# SCH_rhythm-pad_2026-10-07.net
KiCad netlist of a schematic drawn in EasyEDA
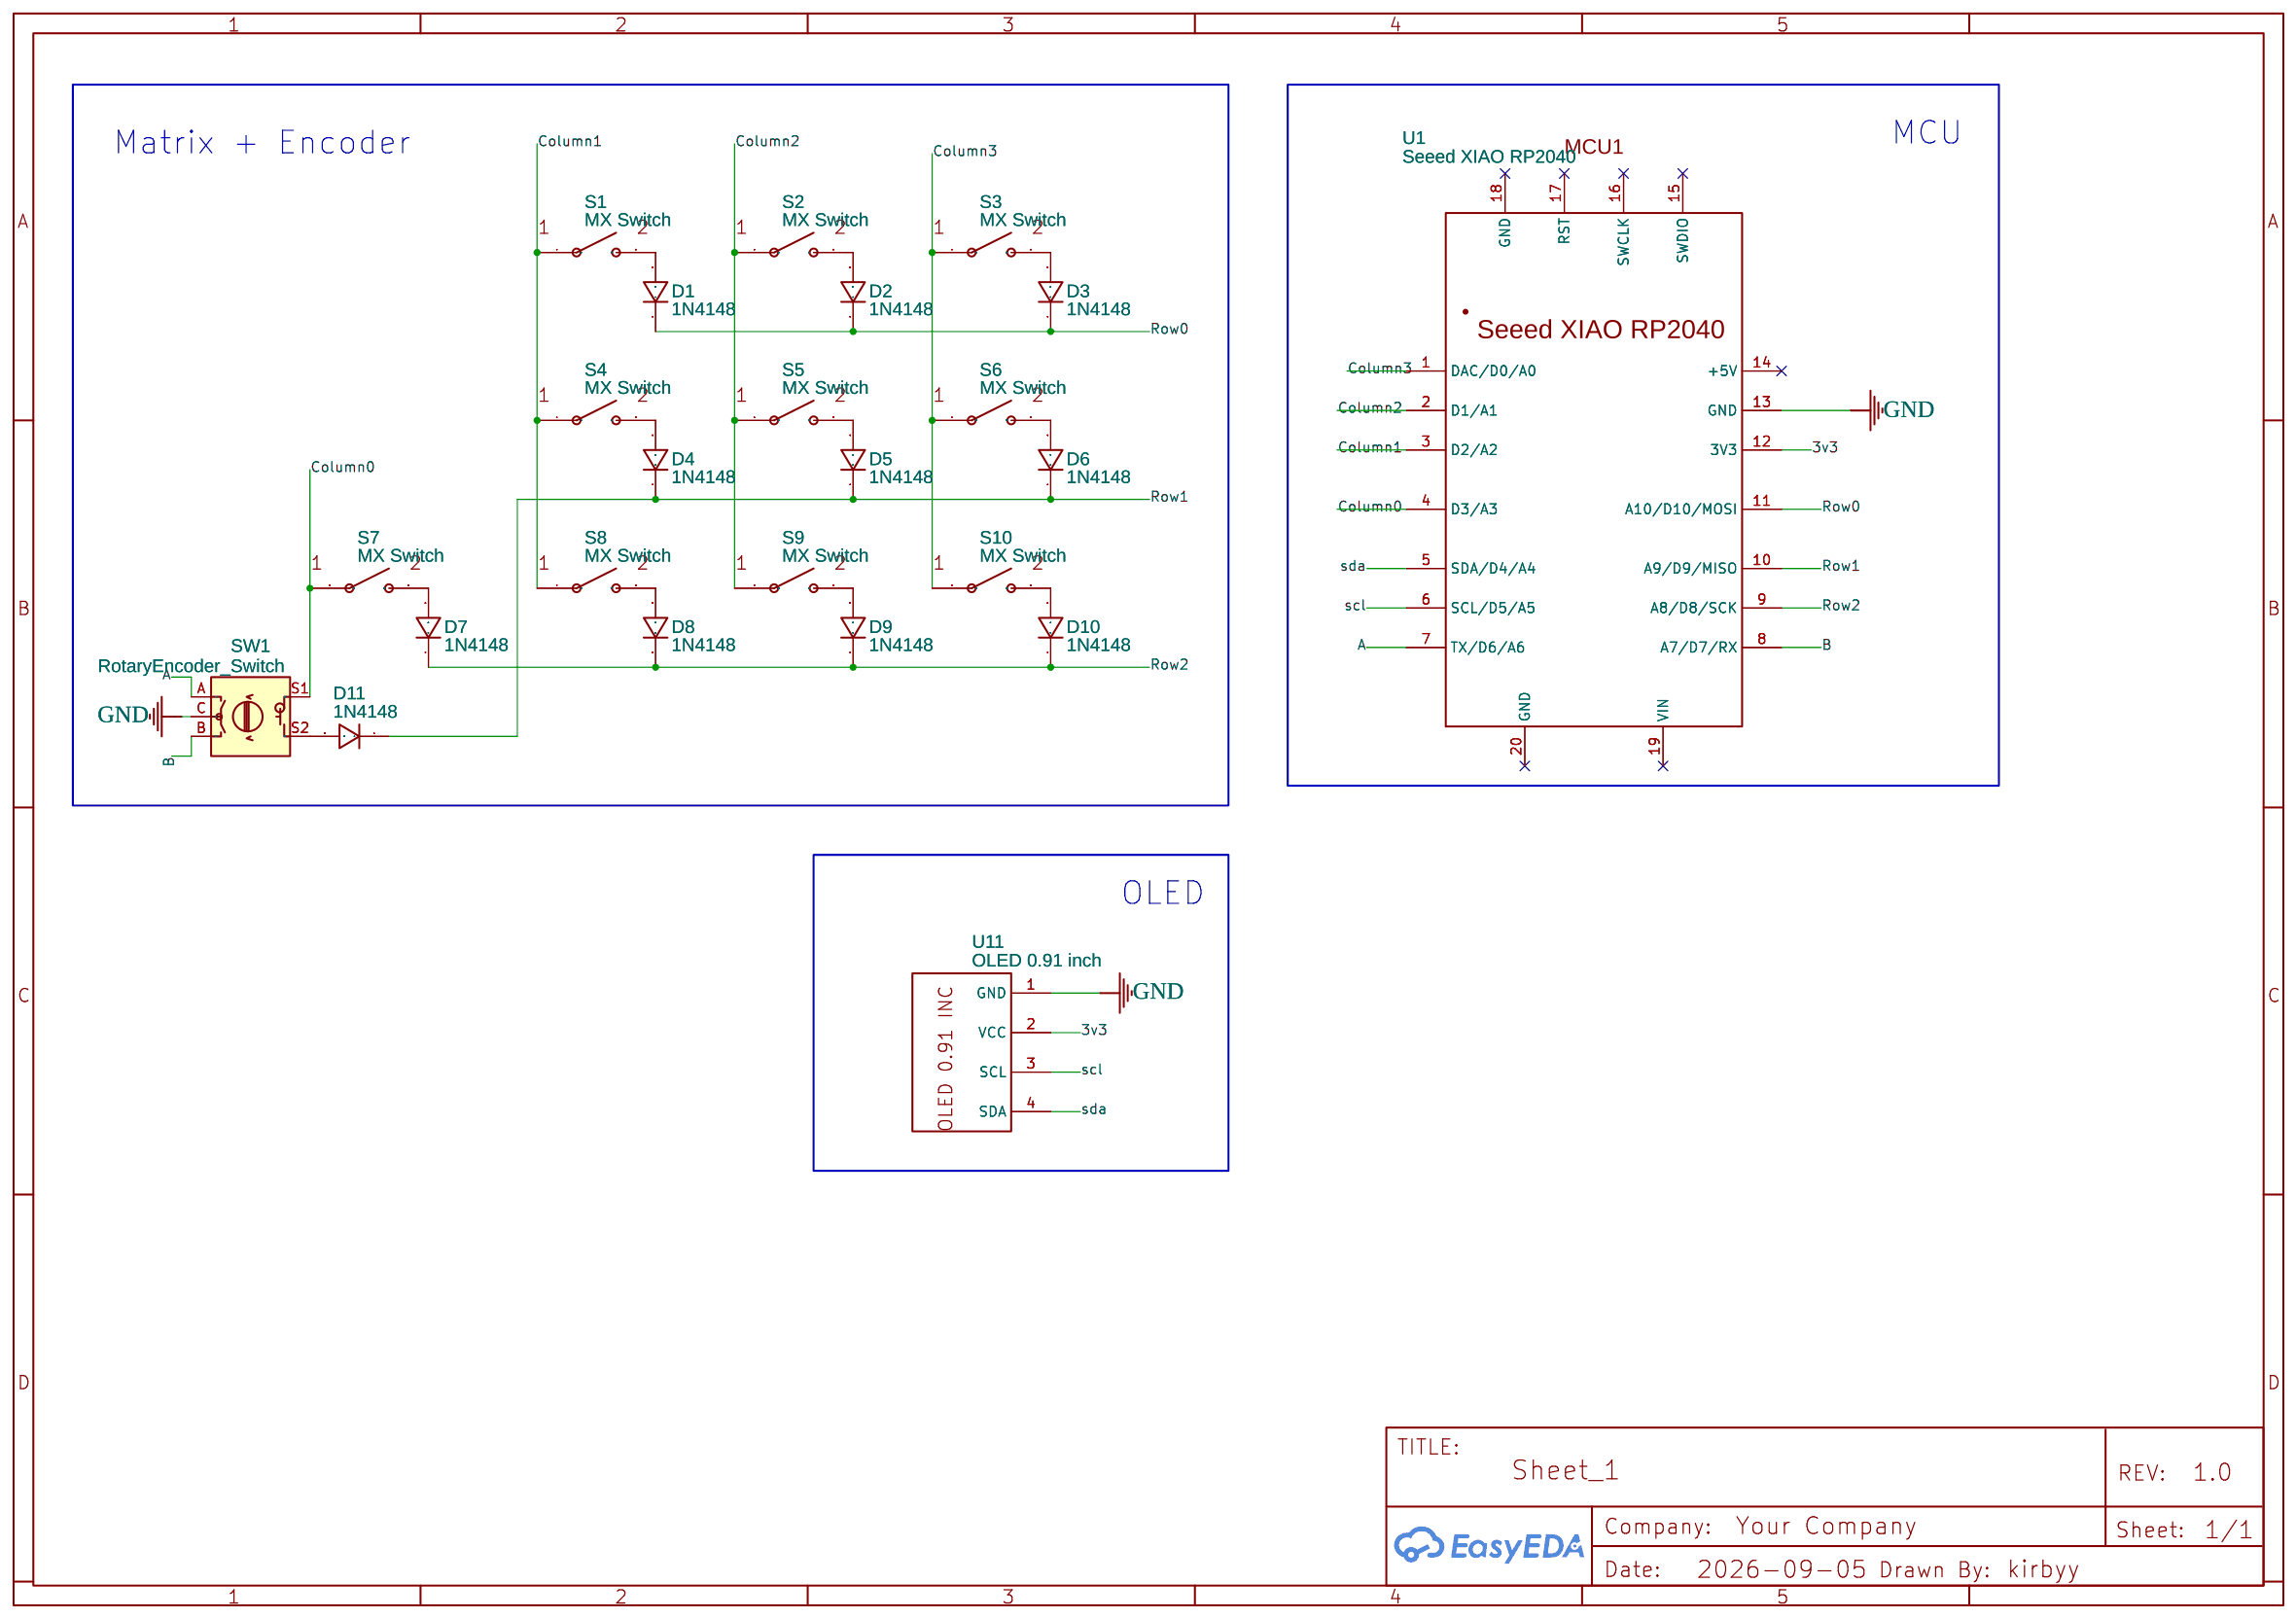
[diagram p0: schematic sheet]

(export (version "E")
  (design (tool "Eeschema 10.0.6"))
  (components
    (comp (ref "D1")
      (value "1N4148")
      (fields (field (name "Manufacturer") "STMicroelectronics"))
      (libsource (lib "") (part "1N4148"))
    )
    (comp (ref "D2")
      (value "1N4148")
      (fields (field (name "Manufacturer") "STMicroelectronics"))
      (libsource (lib "") (part "1N4148"))
    )
    (comp (ref "D3")
      (value "1N4148")
      (fields (field (name "Manufacturer") "STMicroelectronics"))
      (libsource (lib "") (part "1N4148"))
    )
    (comp (ref "D4")
      (value "1N4148")
      (fields (field (name "Manufacturer") "STMicroelectronics"))
      (libsource (lib "") (part "1N4148"))
    )
    (comp (ref "D5")
      (value "1N4148")
      (fields (field (name "Manufacturer") "STMicroelectronics"))
      (libsource (lib "") (part "1N4148"))
    )
    (comp (ref "D6")
      (value "1N4148")
      (fields (field (name "Manufacturer") "STMicroelectronics"))
      (libsource (lib "") (part "1N4148"))
    )
    (comp (ref "D7")
      (value "1N4148")
      (fields (field (name "Manufacturer") "STMicroelectronics"))
      (libsource (lib "") (part "1N4148"))
    )
    (comp (ref "D8")
      (value "1N4148")
      (fields (field (name "Manufacturer") "STMicroelectronics"))
      (libsource (lib "") (part "1N4148"))
    )
    (comp (ref "D9")
      (value "1N4148")
      (fields (field (name "Manufacturer") "STMicroelectronics"))
      (libsource (lib "") (part "1N4148"))
    )
    (comp (ref "D10")
      (value "1N4148")
      (fields (field (name "Manufacturer") "STMicroelectronics"))
      (libsource (lib "") (part "1N4148"))
    )
    (comp (ref "D11")
      (value "1N4148")
      (fields (field (name "Manufacturer") "STMicroelectronics"))
      (libsource (lib "") (part "1N4148_1"))
    )
    (comp (ref "S1") (value "MX Switch") (libsource (lib "") (part "Cherry MX Mechanical Keyboard Switch")))
    (comp (ref "S2") (value "MX Switch") (libsource (lib "") (part "Cherry MX Mechanical Keyboard Switch")))
    (comp (ref "S3") (value "MX Switch") (libsource (lib "") (part "Cherry MX Mechanical Keyboard Switch")))
    (comp (ref "S4") (value "MX Switch") (libsource (lib "") (part "Cherry MX Mechanical Keyboard Switch")))
    (comp (ref "S5") (value "MX Switch") (libsource (lib "") (part "Cherry MX Mechanical Keyboard Switch")))
    (comp (ref "S6") (value "MX Switch") (libsource (lib "") (part "Cherry MX Mechanical Keyboard Switch")))
    (comp (ref "S7") (value "MX Switch") (libsource (lib "") (part "Cherry MX Mechanical Keyboard Switch")))
    (comp (ref "S8") (value "MX Switch") (libsource (lib "") (part "Cherry MX Mechanical Keyboard Switch")))
    (comp (ref "S9") (value "MX Switch") (libsource (lib "") (part "Cherry MX Mechanical Keyboard Switch")))
    (comp (ref "S10") (value "MX Switch") (libsource (lib "") (part "Cherry MX Mechanical Keyboard Switch")))
    (comp (ref "SW1") (value "RotaryEncoder_Switch") (libsource (lib "") (part "RotaryEncoder_Switch")))
    (comp (ref "U1")
      (value "Seeed XIAO RP2040")
      (fields (field (name "Manufacturer Part") "Seeed XIAO RP2040("))
      (libsource (lib "") (part "Seeed XIAO RP2040"))
    )
    (comp (ref "U11") (value "OLED 0.91 inch") (libsource (lib "") (part "OLED 0.91 inch")))
  )
  (nets
    (net (code "1") (name "/3v3") (class "Default")
      (node (ref "U1") (pin "12") (pinfunction "3V3_12") (pintype "unspecified"))
      (node (ref "U11") (pin "2") (pinfunction "VCC_2") (pintype "unspecified"))
    )
    (net (code "2") (name "/A") (class "Default")
      (node (ref "SW1") (pin "A") (pinfunction "A_A") (pintype "unspecified"))
      (node (ref "U1") (pin "7") (pinfunction "TX/D6/A6_7") (pintype "unspecified"))
    )
    (net (code "3") (name "/B") (class "Default")
      (node (ref "SW1") (pin "B") (pinfunction "B_B") (pintype "unspecified"))
      (node (ref "U1") (pin "8") (pinfunction "A7/D7/RX_8") (pintype "unspecified"))
    )
    (net (code "4") (name "/Column0") (class "Default")
      (node (ref "S7") (pin "1") (pinfunction "1_1") (pintype "unspecified"))
      (node (ref "SW1") (pin "S1") (pinfunction "S1_S1") (pintype "unspecified"))
      (node (ref "U1") (pin "4") (pinfunction "D3/A3_4") (pintype "unspecified"))
    )
    (net (code "5") (name "/Column1") (class "Default")
      (node (ref "S1") (pin "1") (pinfunction "1_1") (pintype "unspecified"))
      (node (ref "S4") (pin "1") (pinfunction "1_1") (pintype "unspecified"))
      (node (ref "S8") (pin "1") (pinfunction "1_1") (pintype "unspecified"))
      (node (ref "U1") (pin "3") (pinfunction "D2/A2_3") (pintype "unspecified"))
    )
    (net (code "6") (name "/Column2") (class "Default")
      (node (ref "S2") (pin "1") (pinfunction "1_1") (pintype "unspecified"))
      (node (ref "S5") (pin "1") (pinfunction "1_1") (pintype "unspecified"))
      (node (ref "S9") (pin "1") (pinfunction "1_1") (pintype "unspecified"))
      (node (ref "U1") (pin "2") (pinfunction "D1/A1_2") (pintype "unspecified"))
    )
    (net (code "7") (name "/Column3") (class "Default")
      (node (ref "S10") (pin "1") (pinfunction "1_1") (pintype "unspecified"))
      (node (ref "S3") (pin "1") (pinfunction "1_1") (pintype "unspecified"))
      (node (ref "S6") (pin "1") (pinfunction "1_1") (pintype "unspecified"))
      (node (ref "U1") (pin "1") (pinfunction "DAC/D0/A0_1") (pintype "unspecified"))
    )
    (net (code "8") (name "/Row0") (class "Default")
      (node (ref "D1") (pin "1") (pinfunction "1_1") (pintype "unspecified"))
      (node (ref "D2") (pin "1") (pinfunction "1_1") (pintype "unspecified"))
      (node (ref "D3") (pin "1") (pinfunction "1_1") (pintype "unspecified"))
      (node (ref "U1") (pin "11") (pinfunction "A10/D10/MOSI_11") (pintype "unspecified"))
    )
    (net (code "9") (name "/Row1") (class "Default")
      (node (ref "D11") (pin "1") (pinfunction "1_1") (pintype "unspecified"))
      (node (ref "D4") (pin "1") (pinfunction "1_1") (pintype "unspecified"))
      (node (ref "D5") (pin "1") (pinfunction "1_1") (pintype "unspecified"))
      (node (ref "D6") (pin "1") (pinfunction "1_1") (pintype "unspecified"))
      (node (ref "U1") (pin "10") (pinfunction "A9/D9/MISO_10") (pintype "unspecified"))
    )
    (net (code "10") (name "/Row2") (class "Default")
      (node (ref "D10") (pin "1") (pinfunction "1_1") (pintype "unspecified"))
      (node (ref "D7") (pin "1") (pinfunction "1_1") (pintype "unspecified"))
      (node (ref "D8") (pin "1") (pinfunction "1_1") (pintype "unspecified"))
      (node (ref "D9") (pin "1") (pinfunction "1_1") (pintype "unspecified"))
      (node (ref "U1") (pin "9") (pinfunction "A8/D8/SCK_9") (pintype "unspecified"))
    )
    (net (code "11") (name "/scl") (class "Default")
      (node (ref "U1") (pin "6") (pinfunction "SCL/D5/A5_6") (pintype "unspecified"))
      (node (ref "U11") (pin "3") (pinfunction "SCL_3") (pintype "unspecified"))
    )
    (net (code "12") (name "/sda") (class "Default")
      (node (ref "U1") (pin "5") (pinfunction "SDA/D4/A4_5") (pintype "unspecified"))
      (node (ref "U11") (pin "4") (pinfunction "SDA_4") (pintype "unspecified"))
    )
    (net (code "13") (name "GND") (class "Default")
      (node (ref "SW1") (pin "C") (pinfunction "C_C") (pintype "unspecified"))
      (node (ref "U1") (pin "13") (pinfunction "GND_13") (pintype "unspecified"))
      (node (ref "U11") (pin "1") (pinfunction "GND_1") (pintype "unspecified"))
    )
    (net (code "14") (name "Net-(D1-Pad2)") (class "Default")
      (node (ref "D1") (pin "2") (pinfunction "2_2") (pintype "unspecified"))
      (node (ref "S1") (pin "2") (pinfunction "2_2") (pintype "unspecified"))
    )
    (net (code "15") (name "Net-(D2-Pad2)") (class "Default")
      (node (ref "D2") (pin "2") (pinfunction "2_2") (pintype "unspecified"))
      (node (ref "S2") (pin "2") (pinfunction "2_2") (pintype "unspecified"))
    )
    (net (code "16") (name "Net-(D3-Pad2)") (class "Default")
      (node (ref "D3") (pin "2") (pinfunction "2_2") (pintype "unspecified"))
      (node (ref "S3") (pin "2") (pinfunction "2_2") (pintype "unspecified"))
    )
    (net (code "17") (name "Net-(D4-Pad2)") (class "Default")
      (node (ref "D4") (pin "2") (pinfunction "2_2") (pintype "unspecified"))
      (node (ref "S4") (pin "2") (pinfunction "2_2") (pintype "unspecified"))
    )
    (net (code "18") (name "Net-(D5-Pad2)") (class "Default")
      (node (ref "D5") (pin "2") (pinfunction "2_2") (pintype "unspecified"))
      (node (ref "S5") (pin "2") (pinfunction "2_2") (pintype "unspecified"))
    )
    (net (code "19") (name "Net-(D6-Pad2)") (class "Default")
      (node (ref "D6") (pin "2") (pinfunction "2_2") (pintype "unspecified"))
      (node (ref "S6") (pin "2") (pinfunction "2_2") (pintype "unspecified"))
    )
    (net (code "20") (name "Net-(D7-Pad2)") (class "Default")
      (node (ref "D7") (pin "2") (pinfunction "2_2") (pintype "unspecified"))
      (node (ref "S7") (pin "2") (pinfunction "2_2") (pintype "unspecified"))
    )
    (net (code "21") (name "Net-(D8-Pad2)") (class "Default")
      (node (ref "D8") (pin "2") (pinfunction "2_2") (pintype "unspecified"))
      (node (ref "S8") (pin "2") (pinfunction "2_2") (pintype "unspecified"))
    )
    (net (code "22") (name "Net-(D9-Pad2)") (class "Default")
      (node (ref "D9") (pin "2") (pinfunction "2_2") (pintype "unspecified"))
      (node (ref "S9") (pin "2") (pinfunction "2_2") (pintype "unspecified"))
    )
    (net (code "23") (name "Net-(D10-Pad2)") (class "Default")
      (node (ref "D10") (pin "2") (pinfunction "2_2") (pintype "unspecified"))
      (node (ref "S10") (pin "2") (pinfunction "2_2") (pintype "unspecified"))
    )
    (net (code "24") (name "Net-(D11-Pad2)") (class "Default")
      (node (ref "D11") (pin "2") (pinfunction "2_2") (pintype "unspecified"))
      (node (ref "SW1") (pin "S2") (pinfunction "S2_S2") (pintype "unspecified"))
    )
    (net (code "25") (name "unconnected-(U1-+5V-Pad14)") (class "Default")
      (node (ref "U1") (pin "14") (pinfunction "+5V_14") (pintype "unspecified+no_connect"))
    )
    (net (code "26") (name "unconnected-(U1-GND-Pad18)") (class "Default")
      (node (ref "U1") (pin "18") (pinfunction "GND_18") (pintype "unspecified+no_connect"))
    )
    (net (code "27") (name "unconnected-(U1-GND-Pad20)") (class "Default")
      (node (ref "U1") (pin "20") (pinfunction "GND_20") (pintype "unspecified+no_connect"))
    )
    (net (code "28") (name "unconnected-(U1-RST-Pad17)") (class "Default")
      (node (ref "U1") (pin "17") (pinfunction "RST_17") (pintype "unspecified+no_connect"))
    )
    (net (code "29") (name "unconnected-(U1-SWCLK-Pad16)") (class "Default")
      (node (ref "U1") (pin "16") (pinfunction "SWCLK_16") (pintype "unspecified+no_connect"))
    )
    (net (code "30") (name "unconnected-(U1-SWDIO-Pad15)") (class "Default")
      (node (ref "U1") (pin "15") (pinfunction "SWDIO_15") (pintype "unspecified+no_connect"))
    )
    (net (code "31") (name "unconnected-(U1-VIN-Pad19)") (class "Default")
      (node (ref "U1") (pin "19") (pinfunction "VIN_19") (pintype "unspecified+no_connect"))
    )
  )
)
